# antennas.net
KiCad netlist of a schematic drawn in Altium Designer
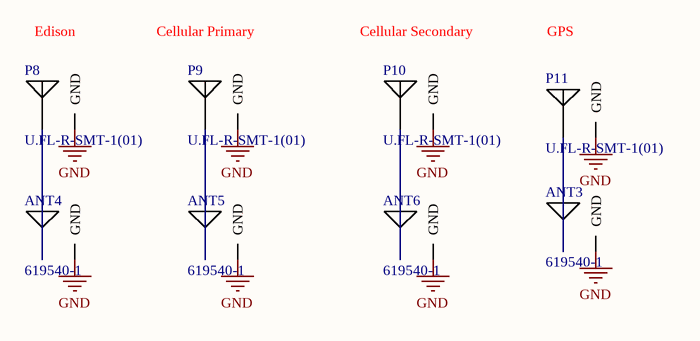
[diagram p0: antennas.SchDoc]

(export (version "E")
  (design (tool "Eeschema 10.0.6"))
  (components
    (comp (ref "ANT3")
      (value "619540-1")
      (footprint "619540-1")
      (description "CONN SMA JACK")
      (libsource (lib "RF") (part "619540-1"))
    )
    (comp (ref "ANT4")
      (value "619540-1")
      (footprint "619540-1")
      (description "CONN SMA JACK")
      (libsource (lib "RF") (part "619540-1"))
    )
    (comp (ref "ANT5")
      (value "619540-1")
      (footprint "619540-1")
      (description "CONN SMA JACK")
      (libsource (lib "RF") (part "619540-1"))
    )
    (comp (ref "ANT6")
      (value "619540-1")
      (footprint "619540-1")
      (description "CONN SMA JACK")
      (libsource (lib "RF") (part "619540-1"))
    )
    (comp (ref "P8")
      (value "U.FL-R-SMT-1(01)")
      (footprint "U.FL-R-SMT-1(01)")
      (description "U.FL, Ultra Miniature Coaxial Connector Receptacle, Male Pin 50 Ohm Surface Mount Solder")
      (libsource (lib "RF") (part "U.FL-R-SMT-1(01)"))
    )
    (comp (ref "P9")
      (value "U.FL-R-SMT-1(01)")
      (footprint "U.FL-R-SMT-1(01)")
      (description "U.FL, Ultra Miniature Coaxial Connector Receptacle, Male Pin 50 Ohm Surface Mount Solder")
      (libsource (lib "RF") (part "U.FL-R-SMT-1(01)"))
    )
    (comp (ref "P10")
      (value "U.FL-R-SMT-1(01)")
      (footprint "U.FL-R-SMT-1(01)")
      (description "U.FL, Ultra Miniature Coaxial Connector Receptacle, Male Pin 50 Ohm Surface Mount Solder")
      (libsource (lib "RF") (part "U.FL-R-SMT-1(01)"))
    )
    (comp (ref "P11")
      (value "U.FL-R-SMT-1(01)")
      (footprint "U.FL-R-SMT-1(01)")
      (description "U.FL, Ultra Miniature Coaxial Connector Receptacle, Male Pin 50 Ohm Surface Mount Solder")
      (libsource (lib "RF") (part "U.FL-R-SMT-1(01)"))
    )
  )
  (nets
    (net (code "1") (name "GND") (class "Default")
      (node (ref "ANT3") (pin "1") (pinfunction "GND_1") (pintype "power_in"))
      (node (ref "ANT4") (pin "1") (pinfunction "GND_1") (pintype "power_in"))
      (node (ref "ANT5") (pin "1") (pinfunction "GND_1") (pintype "power_in"))
      (node (ref "ANT6") (pin "1") (pinfunction "GND_1") (pintype "power_in"))
      (node (ref "P10") (pin "1") (pinfunction "GND_1") (pintype "power_in"))
      (node (ref "P11") (pin "1") (pinfunction "GND_1") (pintype "power_in"))
      (node (ref "P8") (pin "1") (pinfunction "GND_1") (pintype "power_in"))
      (node (ref "P9") (pin "1") (pinfunction "GND_1") (pintype "power_in"))
    )
    (net (code "2") (name "Net-(ANT3-Pad2)") (class "Default")
      (node (ref "ANT3") (pin "2") (pintype "passive"))
      (node (ref "P11") (pin "2") (pintype "passive"))
    )
    (net (code "3") (name "Net-(ANT4-Pad2)") (class "Default")
      (node (ref "ANT4") (pin "2") (pintype "passive"))
      (node (ref "P8") (pin "2") (pintype "passive"))
    )
    (net (code "4") (name "Net-(ANT5-Pad2)") (class "Default")
      (node (ref "ANT5") (pin "2") (pintype "passive"))
      (node (ref "P9") (pin "2") (pintype "passive"))
    )
    (net (code "5") (name "Net-(ANT6-Pad2)") (class "Default")
      (node (ref "ANT6") (pin "2") (pintype "passive"))
      (node (ref "P10") (pin "2") (pintype "passive"))
    )
  )
)
